# Interfaces.net
KiCad netlist of a schematic drawn in Altium Designer
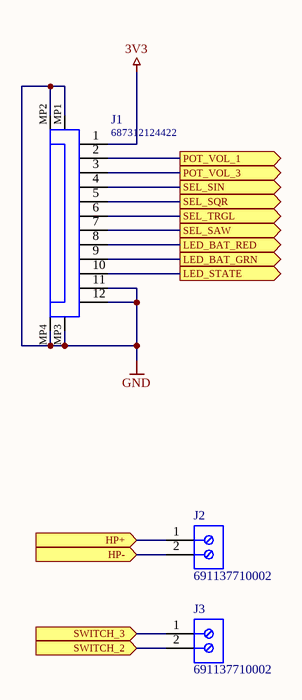
[diagram p0: Interfaces.SchDoc]

(export (version "E")
  (design (tool "Eeschema 10.0.6"))
  (components
    (comp (ref "J1")
      (value "687312124422")
      (footprint "687312124422")
      (description "SMT ZIF Connectors WR-FPC, Vertical, Type A, pitch 0.5 mm, 12 pins")
      (fields (field (name "MANUFACTURER") "Wurth Elektronik") (field (name "PUBLISHER") "WurthElektronik"))
      (libsource (lib "Altium Content Vault") (part "WE-68XX121XXX22-12"))
    )
    (comp (ref "J2")
      (value "691137710002")
      (footprint "691137710002")
      (description "Series 1377 - 5.00 mm Horizontal Entry with Pressure Clamp WR-TBL, 2 pin")
      (fields (field (name "MANUFACTURER") "Wurth Elektronik") (field (name "PUBLISHER") "WurthElektronik"))
      (libsource (lib "Altium Content Vault") (part "WE-CN-1P-F-TB2"))
    )
    (comp (ref "J3")
      (value "691137710002")
      (footprint "691137710002")
      (description "Series 1377 - 5.00 mm Horizontal Entry with Pressure Clamp WR-TBL, 2 pin")
      (fields (field (name "MANUFACTURER") "Wurth Elektronik") (field (name "PUBLISHER") "WurthElektronik"))
      (libsource (lib "Altium Content Vault") (part "WE-CN-1P-F-TB2"))
    )
  )
  (nets
    (net (code "1") (name "/HP+") (class "Default")
      (node (ref "J2") (pin "1") (pinfunction "1_1") (pintype "passive"))
    )
    (net (code "2") (name "/HP-") (class "Default")
      (node (ref "J2") (pin "2") (pinfunction "2_2") (pintype "passive"))
    )
    (net (code "3") (name "/LED_BAT_GRN") (class "Default")
      (node (ref "J1") (pin "9") (pinfunction "9_9") (pintype "passive"))
    )
    (net (code "4") (name "/LED_BAT_RED") (class "Default")
      (node (ref "J1") (pin "8") (pinfunction "8_8") (pintype "passive"))
    )
    (net (code "5") (name "/LED_STATE") (class "Default")
      (node (ref "J1") (pin "10") (pinfunction "10_10") (pintype "passive"))
    )
    (net (code "6") (name "/POT_VOL_1") (class "Default")
      (node (ref "J1") (pin "2") (pinfunction "2_2") (pintype "passive"))
    )
    (net (code "7") (name "/POT_VOL_3") (class "Default")
      (node (ref "J1") (pin "3") (pinfunction "3_3") (pintype "passive"))
    )
    (net (code "8") (name "/SEL_SAW") (class "Default")
      (node (ref "J1") (pin "7") (pinfunction "7_7") (pintype "passive"))
    )
    (net (code "9") (name "/SEL_SIN") (class "Default")
      (node (ref "J1") (pin "4") (pinfunction "4_4") (pintype "passive"))
    )
    (net (code "10") (name "/SEL_SQR") (class "Default")
      (node (ref "J1") (pin "5") (pinfunction "5_5") (pintype "passive"))
    )
    (net (code "11") (name "/SEL_TRGL") (class "Default")
      (node (ref "J1") (pin "6") (pinfunction "6_6") (pintype "passive"))
    )
    (net (code "12") (name "/SWITCH_2") (class "Default")
      (node (ref "J3") (pin "2") (pinfunction "2_2") (pintype "passive"))
    )
    (net (code "13") (name "/SWITCH_3") (class "Default")
      (node (ref "J3") (pin "1") (pinfunction "1_1") (pintype "passive"))
    )
    (net (code "14") (name "3V3") (class "Default")
      (node (ref "J1") (pin "1") (pinfunction "1_1") (pintype "passive"))
    )
    (net (code "15") (name "GND") (class "Default")
      (node (ref "J1") (pin "11") (pinfunction "11_11") (pintype "passive"))
      (node (ref "J1") (pin "12") (pinfunction "12_12") (pintype "passive"))
      (node (ref "J1") (pin "MP1") (pinfunction "MP1_MP1") (pintype "passive"))
      (node (ref "J1") (pin "MP2") (pinfunction "MP2_MP2") (pintype "passive"))
      (node (ref "J1") (pin "MP3") (pinfunction "MP3_MP3") (pintype "passive"))
      (node (ref "J1") (pin "MP4") (pinfunction "MP4_MP4") (pintype "passive"))
    )
  )
)
